# mcu.net
KiCad netlist of a schematic drawn in Altium Designer
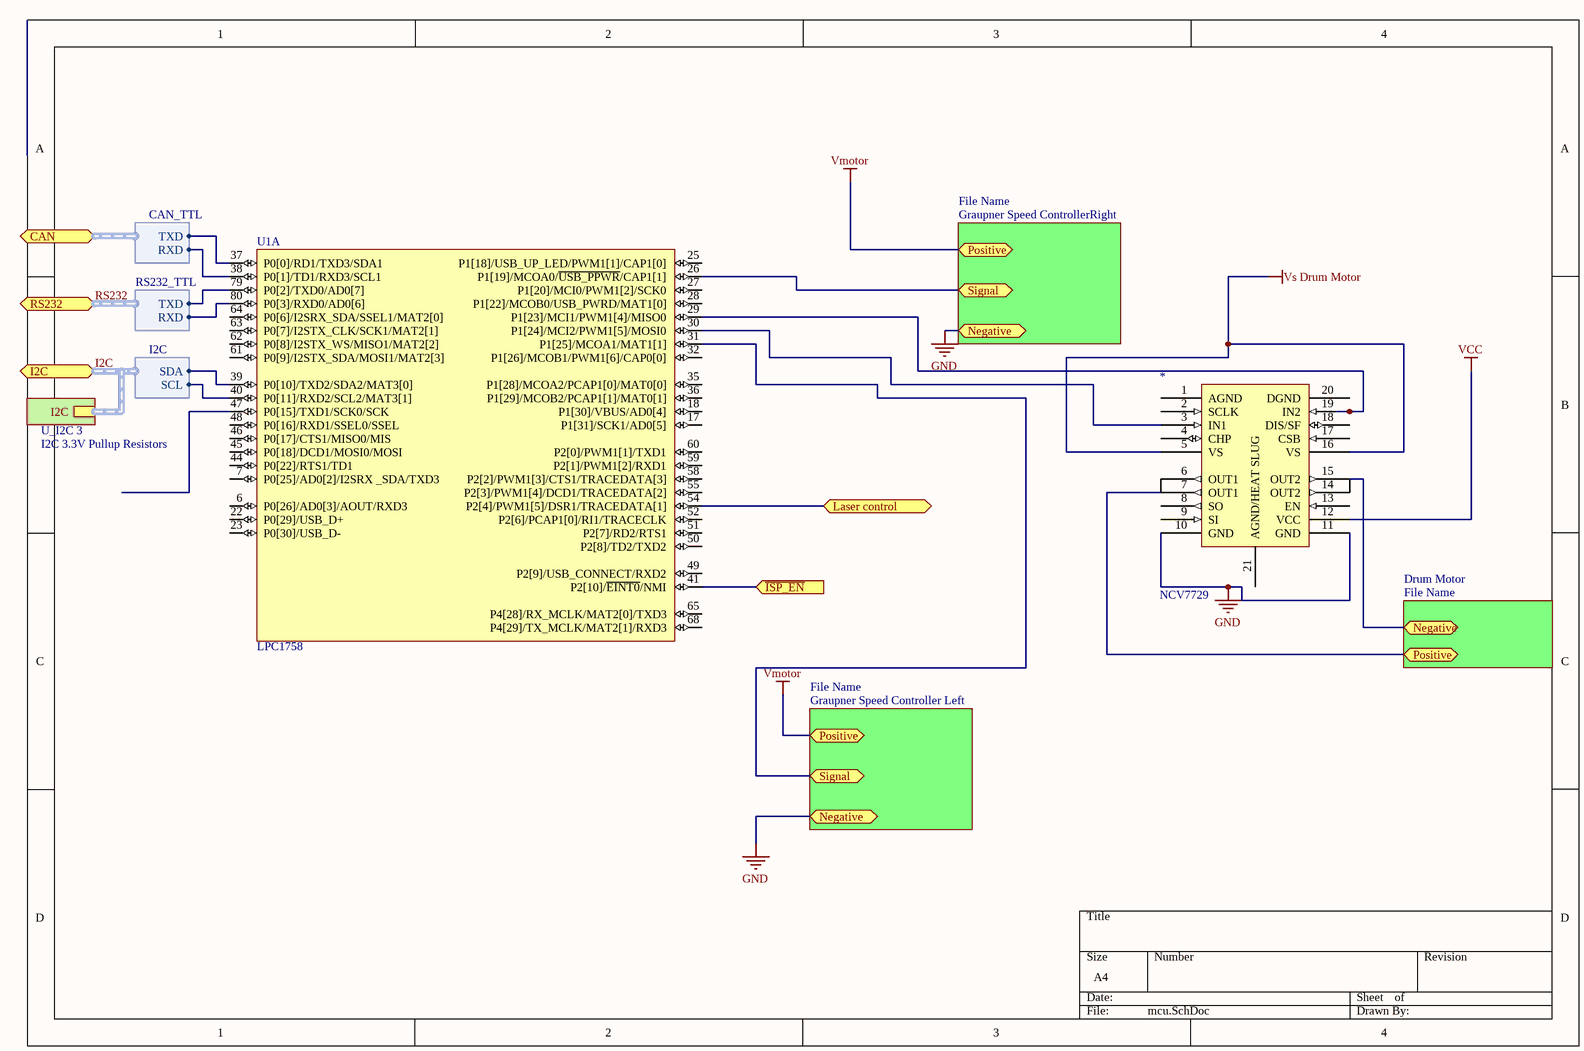
[diagram p0: mcu.SchDoc]

(export (version "E")
  (design (tool "Eeschema 10.0.6"))
  (components
    (comp (ref "*") (value "NCV7729") (footprint "NCV7729") (libsource (lib "NCV7729") (part "NCV7729")))
    (comp (ref "U1")
      (value "LPC1758")
      (footprint "LPC1758FBD80")
      (description "NXP - LPC1758FBD80 - MCU, 32BIT, ARM CORTEX M3, 80LQFP")
      (libsource (lib "LPC1758") (part "LPC1758"))
    )
  )
  (nets
    (net (code "6") (name "/Laser control") (class "Default")
      (node (ref "U1") (pin "54") (pinfunction "P2[4]/PWM1[5]/DSR1/TRACEDATA[1]_54") (pintype "bidirectional"))
    )
    (net (code "8") (name "/SCL") (class "Default")
      (node (ref "U1") (pin "40") (pinfunction "P0[11]/RXD2/SCL2/MAT3[1]_40") (pintype "bidirectional"))
    )
    (net (code "9") (name "/SDA") (class "Default")
      (node (ref "U1") (pin "39") (pinfunction "P0[10]/TXD2/SDA2/MAT3[0]_39") (pintype "bidirectional"))
    )
    (net (code "10") (name "/Signal") (class "Default")
      (node (ref "U1") (pin "26") (pinfunction "P1[19]/MCOA0/~{USB_PPWR}/CAP1[1]_26") (pintype "bidirectional"))
      (node (ref "U1") (pin "31") (pinfunction "P1[25]/MCOA1/MAT1[1]_31") (pintype "bidirectional"))
    )
    (net (code "12") (name "/~{ISP_EN}") (class "Default")
      (node (ref "U1") (pin "41") (pinfunction "P2[10]/~{EINT0}/NMI_41") (pintype "bidirectional"))
    )
    (net (code "13") (name "GND") (class "Default")
      (node (ref "*") (pin "10") (pinfunction "GND_10") (pintype "power_in"))
      (node (ref "*") (pin "11") (pinfunction "GND_11") (pintype "power_in"))
      (node (ref "*") (pin "15") (pinfunction "OUT2_15") (pintype "output"))
    )
    (net (code "14") (name "Net-(*-IN1)") (class "Default")
      (node (ref "*") (pin "3") (pinfunction "IN1_3") (pintype "input"))
      (node (ref "U1") (pin "30") (pinfunction "P1[24]/MCI2/PWM1[5]/MOSI0_30") (pintype "bidirectional"))
    )
    (net (code "15") (name "Net-(*-IN2)") (class "Default")
      (node (ref "*") (pin "19") (pinfunction "IN2_19") (pintype "input"))
      (node (ref "U1") (pin "29") (pinfunction "P1[23]/MCI1/PWM1[4]/MISO0_29") (pintype "bidirectional"))
    )
    (net (code "16") (name "VCC") (class "Default")
      (node (ref "*") (pin "12") (pinfunction "VCC_12") (pintype "power_in"))
    )
    (net (code "17") (name "Vmotor") (class "Default")
      (node (ref "*") (pin "7") (pinfunction "OUT1_7") (pintype "output"))
    )
    (net (code "18") (name "Vs Drum Motor") (class "Default")
      (node (ref "*") (pin "16") (pinfunction "VS_16") (pintype "power_in"))
      (node (ref "*") (pin "5") (pinfunction "VS_5") (pintype "power_in"))
    )
    (net (code "19") (name "unconnected-(*-AGND-Pad1)") (class "Default")
      (node (ref "*") (pin "1") (pinfunction "AGND_1") (pintype "passive"))
    )
    (net (code "20") (name "unconnected-(*-AGND{slash}HEAT_SLUG-Pad21)") (class "Default")
      (node (ref "*") (pin "21") (pinfunction "AGND/HEAT_SLUG_21") (pintype "passive"))
    )
    (net (code "21") (name "unconnected-(*-CHP-Pad4)") (class "Default")
      (node (ref "*") (pin "4") (pinfunction "CHP_4") (pintype "bidirectional"))
    )
    (net (code "22") (name "unconnected-(*-CSB-Pad17)") (class "Default")
      (node (ref "*") (pin "17") (pinfunction "CSB_17") (pintype "input"))
    )
    (net (code "23") (name "unconnected-(*-DGND-Pad20)") (class "Default")
      (node (ref "*") (pin "20") (pinfunction "DGND_20") (pintype "passive"))
    )
    (net (code "24") (name "unconnected-(*-DIS{slash}SF-Pad18)") (class "Default")
      (node (ref "*") (pin "18") (pinfunction "DIS/SF_18") (pintype "bidirectional"))
    )
    (net (code "25") (name "unconnected-(*-EN-Pad13)") (class "Default")
      (node (ref "*") (pin "13") (pinfunction "EN_13") (pintype "input"))
    )
    (net (code "26") (name "unconnected-(*-OUT1-Pad6)") (class "Default")
      (node (ref "*") (pin "6") (pinfunction "OUT1_6") (pintype "output"))
    )
    (net (code "27") (name "unconnected-(*-OUT2-Pad14)") (class "Default")
      (node (ref "*") (pin "14") (pinfunction "OUT2_14") (pintype "output"))
    )
    (net (code "28") (name "unconnected-(*-SCLK-Pad2)") (class "Default")
      (node (ref "*") (pin "2") (pinfunction "SCLK_2") (pintype "input"))
    )
    (net (code "29") (name "unconnected-(*-SI-Pad9)") (class "Default")
      (node (ref "*") (pin "9") (pinfunction "SI_9") (pintype "input"))
    )
    (net (code "30") (name "unconnected-(*-SO-Pad8)") (class "Default")
      (node (ref "*") (pin "8") (pinfunction "SO_8") (pintype "output"))
    )
    (net (code "31") (name "unconnected-(U1A-P0[0]{slash}RD1{slash}TXD3{slash}SDA1-Pad37)") (class "Default")
      (node (ref "U1") (pin "37") (pinfunction "P0[0]/RD1/TXD3/SDA1_37") (pintype "bidirectional"))
    )
    (net (code "32") (name "unconnected-(U1A-P0[1]{slash}TD1{slash}RXD3{slash}SCL1-Pad38)") (class "Default")
      (node (ref "U1") (pin "38") (pinfunction "P0[1]/TD1/RXD3/SCL1_38") (pintype "bidirectional"))
    )
    (net (code "33") (name "unconnected-(U1A-P0[2]{slash}TXD0{slash}AD0[7]-Pad79)") (class "Default")
      (node (ref "U1") (pin "79") (pinfunction "P0[2]/TXD0/AD0[7]_79") (pintype "bidirectional"))
    )
    (net (code "34") (name "unconnected-(U1A-P0[3]{slash}RXD0{slash}AD0[6]-Pad80)") (class "Default")
      (node (ref "U1") (pin "80") (pinfunction "P0[3]/RXD0/AD0[6]_80") (pintype "bidirectional"))
    )
    (net (code "35") (name "unconnected-(U1A-P0[6]{slash}I2SRX_SDA{slash}SSEL1{slash}MAT2[0]-Pad64)") (class "Default")
      (node (ref "U1") (pin "64") (pinfunction "P0[6]/I2SRX_SDA/SSEL1/MAT2[0]_64") (pintype "bidirectional"))
    )
    (net (code "36") (name "unconnected-(U1A-P0[7]{slash}I2STX_CLK{slash}SCK1{slash}MAT2[1]-Pad63)") (class "Default")
      (node (ref "U1") (pin "63") (pinfunction "P0[7]/I2STX_CLK/SCK1/MAT2[1]_63") (pintype "bidirectional"))
    )
    (net (code "37") (name "unconnected-(U1A-P0[8]{slash}I2STX_WS{slash}MISO1{slash}MAT2[2]-Pad62)") (class "Default")
      (node (ref "U1") (pin "62") (pinfunction "P0[8]/I2STX_WS/MISO1/MAT2[2]_62") (pintype "bidirectional"))
    )
    (net (code "38") (name "unconnected-(U1A-P0[9]{slash}I2STX_SDA{slash}MOSI1{slash}MAT2[3]-Pad61)") (class "Default")
      (node (ref "U1") (pin "61") (pinfunction "P0[9]/I2STX_SDA/MOSI1/MAT2[3]_61") (pintype "bidirectional"))
    )
    (net (code "39") (name "unconnected-(U1A-P0[15]{slash}TXD1{slash}SCK0{slash}SCK-Pad47)") (class "Default")
      (node (ref "U1") (pin "47") (pinfunction "P0[15]/TXD1/SCK0/SCK_47") (pintype "bidirectional"))
    )
    (net (code "40") (name "unconnected-(U1A-P0[16]{slash}RXD1{slash}SSEL0{slash}SSEL-Pad48)") (class "Default")
      (node (ref "U1") (pin "48") (pinfunction "P0[16]/RXD1/SSEL0/SSEL_48") (pintype "bidirectional"))
    )
    (net (code "41") (name "unconnected-(U1A-P0[17]{slash}CTS1{slash}MISO0{slash}MIS-Pad46)") (class "Default")
      (node (ref "U1") (pin "46") (pinfunction "P0[17]/CTS1/MISO0/MIS_46") (pintype "bidirectional"))
    )
    (net (code "42") (name "unconnected-(U1A-P0[18]{slash}DCD1{slash}MOSI0{slash}MOSI-Pad45)") (class "Default")
      (node (ref "U1") (pin "45") (pinfunction "P0[18]/DCD1/MOSI0/MOSI_45") (pintype "bidirectional"))
    )
    (net (code "43") (name "unconnected-(U1A-P0[22]{slash}RTS1{slash}TD1-Pad44)") (class "Default")
      (node (ref "U1") (pin "44") (pinfunction "P0[22]/RTS1/TD1_44") (pintype "bidirectional"))
    )
    (net (code "44") (name "unconnected-(U1A-P0[25]{slash}AD0[2]{slash}I2SRX__SDA{slash}TXD3-Pad7)") (class "Default")
      (node (ref "U1") (pin "7") (pinfunction "P0[25]/AD0[2]/I2SRX__SDA/TXD3_7") (pintype "bidirectional"))
    )
    (net (code "45") (name "unconnected-(U1A-P0[26]{slash}AD0[3]{slash}AOUT{slash}RXD3-Pad6)") (class "Default")
      (node (ref "U1") (pin "6") (pinfunction "P0[26]/AD0[3]/AOUT/RXD3_6") (pintype "bidirectional"))
    )
    (net (code "46") (name "unconnected-(U1A-P0[29]{slash}USB_D+-Pad22)") (class "Default")
      (node (ref "U1") (pin "22") (pinfunction "P0[29]/USB_D+_22") (pintype "bidirectional"))
    )
    (net (code "47") (name "unconnected-(U1A-P0[30]{slash}USB_D--Pad23)") (class "Default")
      (node (ref "U1") (pin "23") (pinfunction "P0[30]/USB_D-_23") (pintype "bidirectional"))
    )
    (net (code "48") (name "unconnected-(U1A-P1[18]{slash}USB_UP_LED{slash}PWM1[1]{slash}CAP1[0]-Pad25)") (class "Default")
      (node (ref "U1") (pin "25") (pinfunction "P1[18]/USB_UP_LED/PWM1[1]/CAP1[0]_25") (pintype "bidirectional"))
    )
    (net (code "49") (name "unconnected-(U1A-P1[20]{slash}MCI0{slash}PWM1[2]{slash}SCK0-Pad27)") (class "Default")
      (node (ref "U1") (pin "27") (pinfunction "P1[20]/MCI0/PWM1[2]/SCK0_27") (pintype "bidirectional"))
    )
    (net (code "50") (name "unconnected-(U1A-P1[22]{slash}MCOB0{slash}USB_PWRD{slash}MAT1[0]-Pad28)") (class "Default")
      (node (ref "U1") (pin "28") (pinfunction "P1[22]/MCOB0/USB_PWRD/MAT1[0]_28") (pintype "bidirectional"))
    )
    (net (code "51") (name "unconnected-(U1A-P1[26]{slash}MCOB1{slash}PWM1[6]{slash}CAP0[0]-Pad32)") (class "Default")
      (node (ref "U1") (pin "32") (pinfunction "P1[26]/MCOB1/PWM1[6]/CAP0[0]_32") (pintype "bidirectional"))
    )
    (net (code "52") (name "unconnected-(U1A-P1[28]{slash}MCOA2{slash}PCAP1[0]{slash}MAT0[0]-Pad35)") (class "Default")
      (node (ref "U1") (pin "35") (pinfunction "P1[28]/MCOA2/PCAP1[0]/MAT0[0]_35") (pintype "bidirectional"))
    )
    (net (code "53") (name "unconnected-(U1A-P1[29]{slash}MCOB2{slash}PCAP1[1]{slash}MAT0[1]-Pad36)") (class "Default")
      (node (ref "U1") (pin "36") (pinfunction "P1[29]/MCOB2/PCAP1[1]/MAT0[1]_36") (pintype "bidirectional"))
    )
    (net (code "54") (name "unconnected-(U1A-P1[30]{slash}VBUS{slash}AD0[4]-Pad18)") (class "Default")
      (node (ref "U1") (pin "18") (pinfunction "P1[30]/VBUS/AD0[4]_18") (pintype "bidirectional"))
    )
    (net (code "55") (name "unconnected-(U1A-P1[31]{slash}SCK1{slash}AD0[5]-Pad17)") (class "Default")
      (node (ref "U1") (pin "17") (pinfunction "P1[31]/SCK1/AD0[5]_17") (pintype "bidirectional"))
    )
    (net (code "56") (name "unconnected-(U1A-P2[0]{slash}PWM1[1]{slash}TXD1-Pad60)") (class "Default")
      (node (ref "U1") (pin "60") (pinfunction "P2[0]/PWM1[1]/TXD1_60") (pintype "bidirectional"))
    )
    (net (code "57") (name "unconnected-(U1A-P2[1]{slash}PWM1[2]{slash}RXD1-Pad59)") (class "Default")
      (node (ref "U1") (pin "59") (pinfunction "P2[1]/PWM1[2]/RXD1_59") (pintype "bidirectional"))
    )
    (net (code "58") (name "unconnected-(U1A-P2[2]{slash}PWM1[3]{slash}CTS1{slash}TRACEDATA[3]-Pad58)") (class "Default")
      (node (ref "U1") (pin "58") (pinfunction "P2[2]/PWM1[3]/CTS1/TRACEDATA[3]_58") (pintype "bidirectional"))
    )
    (net (code "59") (name "unconnected-(U1A-P2[3]{slash}PWM1[4]{slash}DCD1{slash}TRACEDATA[2]-Pad55)") (class "Default")
      (node (ref "U1") (pin "55") (pinfunction "P2[3]/PWM1[4]/DCD1/TRACEDATA[2]_55") (pintype "bidirectional"))
    )
    (net (code "60") (name "unconnected-(U1A-P2[6]{slash}PCAP1[0]{slash}RI1{slash}TRACECLK-Pad52)") (class "Default")
      (node (ref "U1") (pin "52") (pinfunction "P2[6]/PCAP1[0]/RI1/TRACECLK_52") (pintype "bidirectional"))
    )
    (net (code "61") (name "unconnected-(U1A-P2[7]{slash}RD2{slash}RTS1-Pad51)") (class "Default")
      (node (ref "U1") (pin "51") (pinfunction "P2[7]/RD2/RTS1_51") (pintype "bidirectional"))
    )
    (net (code "62") (name "unconnected-(U1A-P2[8]{slash}TD2{slash}TXD2-Pad50)") (class "Default")
      (node (ref "U1") (pin "50") (pinfunction "P2[8]/TD2/TXD2_50") (pintype "bidirectional"))
    )
    (net (code "63") (name "unconnected-(U1A-P2[9]{slash}USB_CONNECT{slash}RXD2-Pad49)") (class "Default")
      (node (ref "U1") (pin "49") (pinfunction "P2[9]/USB_CONNECT/RXD2_49") (pintype "bidirectional"))
    )
    (net (code "64") (name "unconnected-(U1A-P4[28]{slash}RX_MCLK{slash}MAT2[0]{slash}TXD3-Pad65)") (class "Default")
      (node (ref "U1") (pin "65") (pinfunction "P4[28]/RX_MCLK/MAT2[0]/TXD3_65") (pintype "bidirectional"))
    )
    (net (code "65") (name "unconnected-(U1A-P4[29]{slash}TX_MCLK{slash}MAT2[1]{slash}RXD3-Pad68)") (class "Default")
      (node (ref "U1") (pin "68") (pinfunction "P4[29]/TX_MCLK/MAT2[1]/RXD3_68") (pintype "bidirectional"))
    )
  )
)
